# PSU_Schematic.net
KiCad netlist of a schematic drawn in EAGLE
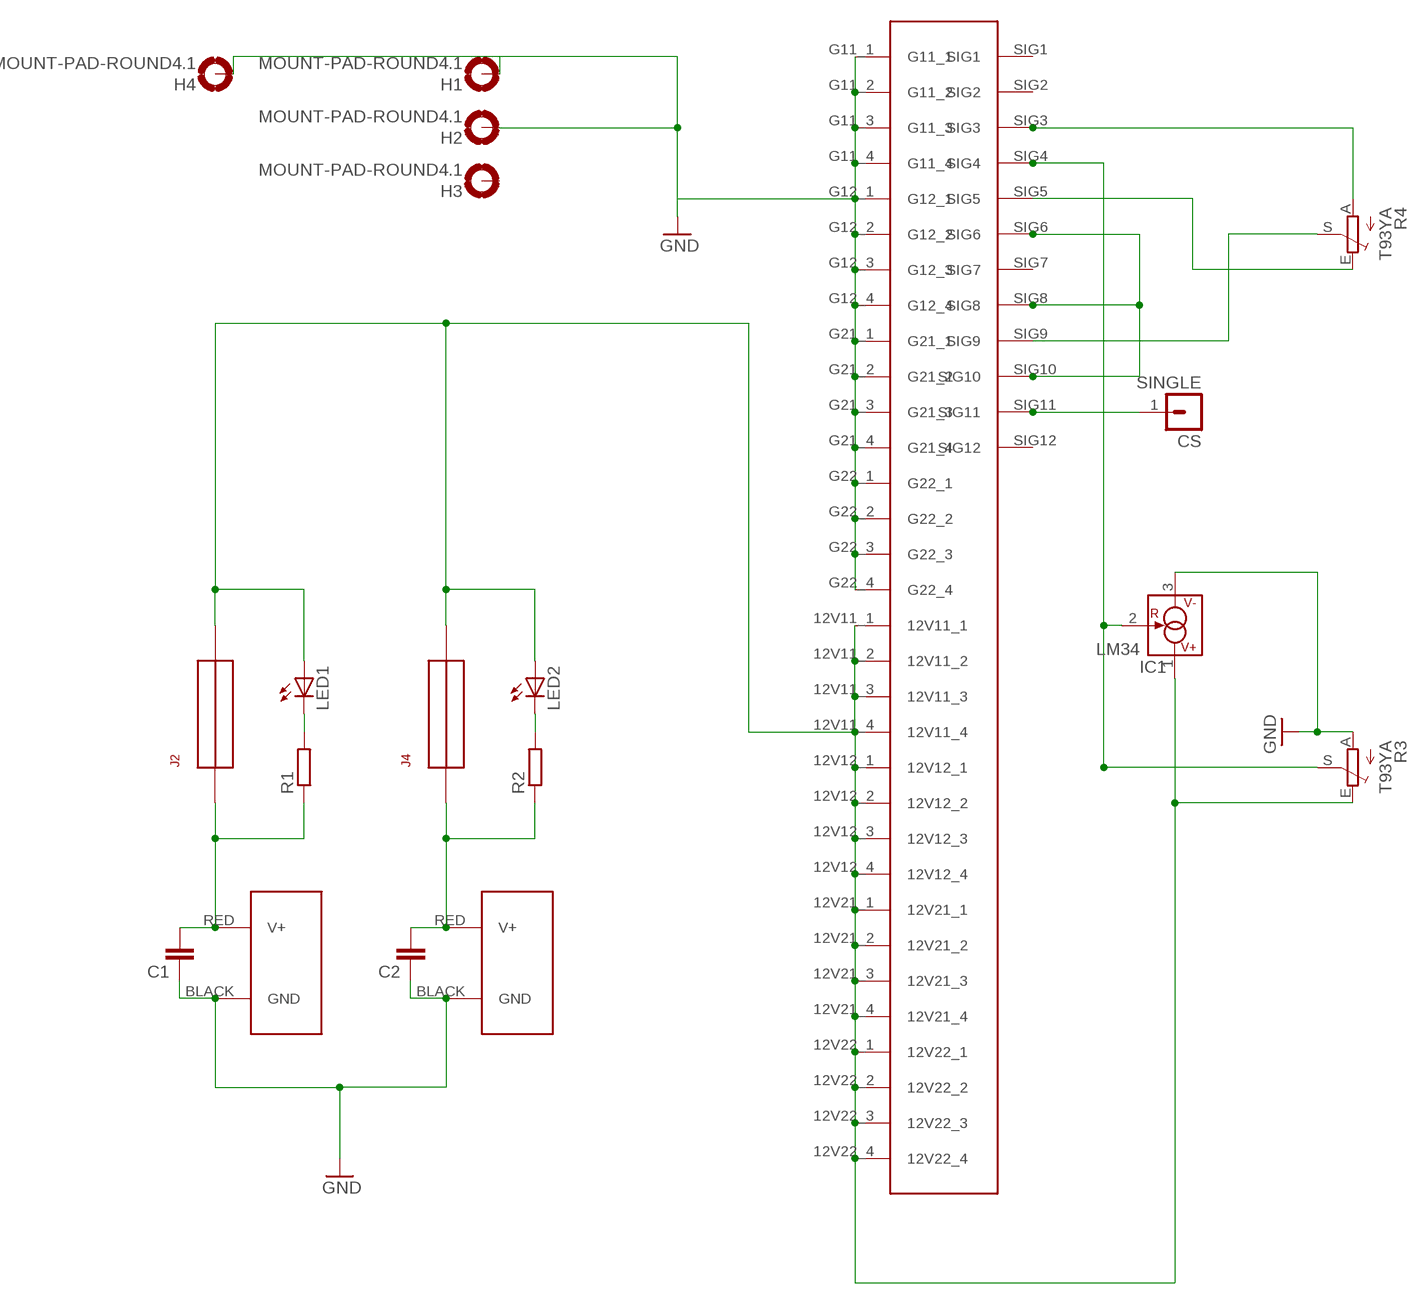
[diagram p0: schematic, sheet 1]

(export (version "E")
  (design (tool "Eeschema 10.0.6"))
  (components
    (comp (ref "C1")
      (value "C-EU050-025X075")
      (footprint "eagle-import:C050-025X075")
      (libsource (lib "eagle-import") (part "C-EU050-025X075"))
    )
    (comp (ref "C2")
      (value "C-EU050-025X075")
      (footprint "eagle-import:C050-025X075")
      (libsource (lib "eagle-import") (part "C-EU050-025X075"))
    )
    (comp (ref "CS")
      (value "SINGLE")
      (footprint "eagle-import:SINGLE")
      (libsource (lib "eagle-import") (part "SINGLE"))
    )
    (comp (ref "H1")
      (value "MOUNT-PAD-ROUND4.1")
      (footprint "eagle-import:4,1-PAD")
      (libsource (lib "eagle-import") (part "MOUNT-PAD-ROUND4.1"))
    )
    (comp (ref "H2")
      (value "MOUNT-PAD-ROUND4.1")
      (footprint "eagle-import:4,1-PAD")
      (libsource (lib "eagle-import") (part "MOUNT-PAD-ROUND4.1"))
    )
    (comp (ref "H3")
      (value "MOUNT-PAD-ROUND4.1")
      (footprint "eagle-import:4,1-PAD")
      (libsource (lib "eagle-import") (part "MOUNT-PAD-ROUND4.1"))
    )
    (comp (ref "H4")
      (value "MOUNT-PAD-ROUND4.1")
      (footprint "eagle-import:4,1-PAD")
      (libsource (lib "eagle-import") (part "MOUNT-PAD-ROUND4.1"))
    )
    (comp (ref "IC1")
      (value "LM34")
      (footprint "eagle-import:TO92")
      (libsource (lib "eagle-import") (part "LM34Z3"))
    )
    (comp (ref "J1")
      (value "POWERPOLE_POWER45A")
      (footprint "eagle-import:POWERPOLE_PAIR_45A")
      (libsource (lib "eagle-import") (part "POWERPOLE_POWER45A"))
    )
    (comp (ref "J2")
      (value "FUSEATC")
      (footprint "eagle-import:FUSE_ATC")
      (libsource (lib "eagle-import") (part "FUSEATC"))
    )
    (comp (ref "J3")
      (value "POWERPOLE_POWER45A")
      (footprint "eagle-import:POWERPOLE_PAIR_45A")
      (libsource (lib "eagle-import") (part "POWERPOLE_POWER45A"))
    )
    (comp (ref "J4")
      (value "FUSEATC")
      (footprint "eagle-import:FUSE_ATC")
      (libsource (lib "eagle-import") (part "FUSEATC"))
    )
    (comp (ref "LED1")
      (value "LED3MM")
      (footprint "eagle-import:LED3MM")
      (libsource (lib "eagle-import") (part "LED3MM"))
    )
    (comp (ref "LED2")
      (value "LED3MM")
      (footprint "eagle-import:LED3MM")
      (libsource (lib "eagle-import") (part "LED3MM"))
    )
    (comp (ref "R1")
      (value "R-EU_0204/7")
      (footprint "eagle-import:0204_7")
      (libsource (lib "eagle-import") (part "R-EU_0204/7"))
    )
    (comp (ref "R2")
      (value "R-EU_0204/7")
      (footprint "eagle-import:0204_7")
      (libsource (lib "eagle-import") (part "R-EU_0204/7"))
    )
    (comp (ref "R3")
      (value "T93YA")
      (footprint "eagle-import:RJ9W")
      (libsource (lib "eagle-import") (part "TRIM_EU-RJ9W"))
    )
    (comp (ref "R4")
      (value "T93YA")
      (footprint "eagle-import:RJ9W")
      (libsource (lib "eagle-import") (part "TRIM_EU-RJ9W"))
    )
    (comp (ref "U$2")
      (value "51760-10201202AALF51760-10201202AALF")
      (footprint "eagle-import:51730-073LF")
      (libsource (lib "eagle-import") (part "51760-10201202AALF51760-10201202AALF"))
    )
  )
  (nets
    (net (code "1") (name "GND") (class "Default")
      (node (ref "C1") (pin "1") (pinfunction "1_1") (pintype "passive"))
      (node (ref "C2") (pin "1") (pinfunction "1_1") (pintype "passive"))
      (node (ref "H1") (pin "B4,1") (pinfunction "MOUNT_B4,1") (pintype "passive"))
      (node (ref "H2") (pin "B4,1") (pinfunction "MOUNT_B4,1") (pintype "passive"))
      (node (ref "H4") (pin "B4,1") (pinfunction "MOUNT_B4,1") (pintype "passive"))
      (node (ref "IC1") (pin "3") (pinfunction "V-_3") (pintype "passive"))
      (node (ref "J1") (pin "BLACK") (pinfunction "GND_BLACK") (pintype "power_in"))
      (node (ref "J3") (pin "BLACK") (pinfunction "GND_BLACK") (pintype "power_in"))
      (node (ref "R3") (pin "A") (pinfunction "A_A") (pintype "passive"))
      (node (ref "U$2") (pin "G11_1") (pinfunction "G11_1_G11_1") (pintype "bidirectional"))
      (node (ref "U$2") (pin "G11_2") (pinfunction "G11_2_G11_2") (pintype "bidirectional"))
      (node (ref "U$2") (pin "G11_3") (pinfunction "G11_3_G11_3") (pintype "bidirectional"))
      (node (ref "U$2") (pin "G11_4") (pinfunction "G11_4_G11_4") (pintype "bidirectional"))
      (node (ref "U$2") (pin "G12_1") (pinfunction "G12_1_G12_1") (pintype "bidirectional"))
      (node (ref "U$2") (pin "G12_2") (pinfunction "G12_2_G12_2") (pintype "bidirectional"))
      (node (ref "U$2") (pin "G12_3") (pinfunction "G12_3_G12_3") (pintype "bidirectional"))
      (node (ref "U$2") (pin "G12_4") (pinfunction "G12_4_G12_4") (pintype "bidirectional"))
      (node (ref "U$2") (pin "G21_1") (pinfunction "G21_1_G21_1") (pintype "bidirectional"))
      (node (ref "U$2") (pin "G21_2") (pinfunction "G21_2_G21_2") (pintype "bidirectional"))
      (node (ref "U$2") (pin "G21_3") (pinfunction "G21_3_G21_3") (pintype "bidirectional"))
      (node (ref "U$2") (pin "G21_4") (pinfunction "G21_4_G21_4") (pintype "bidirectional"))
      (node (ref "U$2") (pin "G22_1") (pinfunction "G22_1_G22_1") (pintype "bidirectional"))
      (node (ref "U$2") (pin "G22_2") (pinfunction "G22_2_G22_2") (pintype "bidirectional"))
      (node (ref "U$2") (pin "G22_3") (pinfunction "G22_3_G22_3") (pintype "bidirectional"))
      (node (ref "U$2") (pin "G22_4") (pinfunction "G22_4_G22_4") (pintype "bidirectional"))
    )
    (net (code "2") (name "Net-(CS-3)") (class "Default")
      (node (ref "CS") (pin "1") (pinfunction "3_1") (pintype "passive"))
      (node (ref "U$2") (pin "SIG11") (pinfunction "SIG11_SIG11") (pintype "bidirectional"))
    )
    (net (code "3") (name "Net-(IC1-R)") (class "Default")
      (node (ref "IC1") (pin "2") (pinfunction "R_2") (pintype "passive"))
      (node (ref "R3") (pin "S") (pinfunction "S_S") (pintype "passive"))
      (node (ref "U$2") (pin "SIG4") (pinfunction "SIG4_SIG4") (pintype "bidirectional"))
    )
    (net (code "4") (name "Net-(IC1-V+)") (class "Default")
      (node (ref "IC1") (pin "1") (pinfunction "V+_1") (pintype "passive"))
      (node (ref "J2") (pin "P$3") (pinfunction "P$2_P$3") (pintype "bidirectional"))
      (node (ref "J2") (pin "P$4") (pinfunction "P$2_P$4") (pintype "bidirectional"))
      (node (ref "J4") (pin "P$3") (pinfunction "P$2_P$3") (pintype "bidirectional"))
      (node (ref "J4") (pin "P$4") (pinfunction "P$2_P$4") (pintype "bidirectional"))
      (node (ref "LED1") (pin "A") (pinfunction "A_A") (pintype "passive"))
      (node (ref "LED2") (pin "A") (pinfunction "A_A") (pintype "passive"))
      (node (ref "R3") (pin "E") (pinfunction "E_E") (pintype "passive"))
      (node (ref "U$2") (pin "12V11_1") (pinfunction "12V11_1_12V11_1") (pintype "bidirectional"))
      (node (ref "U$2") (pin "12V11_2") (pinfunction "12V11_2_12V11_2") (pintype "bidirectional"))
      (node (ref "U$2") (pin "12V11_3") (pinfunction "12V11_3_12V11_3") (pintype "bidirectional"))
      (node (ref "U$2") (pin "12V11_4") (pinfunction "12V11_4_12V11_4") (pintype "bidirectional"))
      (node (ref "U$2") (pin "12V12_1") (pinfunction "12V12_1_12V12_1") (pintype "bidirectional"))
      (node (ref "U$2") (pin "12V12_2") (pinfunction "12V12_2_12V12_2") (pintype "bidirectional"))
      (node (ref "U$2") (pin "12V12_3") (pinfunction "12V12_3_12V12_3") (pintype "bidirectional"))
      (node (ref "U$2") (pin "12V12_4") (pinfunction "12V12_4_12V12_4") (pintype "bidirectional"))
      (node (ref "U$2") (pin "12V21_1") (pinfunction "12V21_1_12V21_1") (pintype "bidirectional"))
      (node (ref "U$2") (pin "12V21_2") (pinfunction "12V21_2_12V21_2") (pintype "bidirectional"))
      (node (ref "U$2") (pin "12V21_3") (pinfunction "12V21_3_12V21_3") (pintype "bidirectional"))
      (node (ref "U$2") (pin "12V21_4") (pinfunction "12V21_4_12V21_4") (pintype "bidirectional"))
      (node (ref "U$2") (pin "12V22_1") (pinfunction "12V22_1_12V22_1") (pintype "bidirectional"))
      (node (ref "U$2") (pin "12V22_2") (pinfunction "12V22_2_12V22_2") (pintype "bidirectional"))
      (node (ref "U$2") (pin "12V22_3") (pinfunction "12V22_3_12V22_3") (pintype "bidirectional"))
      (node (ref "U$2") (pin "12V22_4") (pinfunction "12V22_4_12V22_4") (pintype "bidirectional"))
    )
    (net (code "5") (name "Net-(J1-V+)") (class "Default")
      (node (ref "C1") (pin "2") (pinfunction "2_2") (pintype "passive"))
      (node (ref "J1") (pin "RED") (pinfunction "V+_RED") (pintype "power_in"))
      (node (ref "J2") (pin "P$1") (pinfunction "P$1_P$1") (pintype "bidirectional"))
      (node (ref "J2") (pin "P$2") (pinfunction "P$1_P$2") (pintype "bidirectional"))
      (node (ref "R1") (pin "1") (pinfunction "1_1") (pintype "passive"))
    )
    (net (code "6") (name "Net-(J3-V+)") (class "Default")
      (node (ref "C2") (pin "2") (pinfunction "2_2") (pintype "passive"))
      (node (ref "J3") (pin "RED") (pinfunction "V+_RED") (pintype "power_in"))
      (node (ref "J4") (pin "P$1") (pinfunction "P$1_P$1") (pintype "bidirectional"))
      (node (ref "J4") (pin "P$2") (pinfunction "P$1_P$2") (pintype "bidirectional"))
      (node (ref "R2") (pin "1") (pinfunction "1_1") (pintype "passive"))
    )
    (net (code "7") (name "Net-(LED1-C)") (class "Default")
      (node (ref "LED1") (pin "K") (pinfunction "C_K") (pintype "passive"))
      (node (ref "R1") (pin "2") (pinfunction "2_2") (pintype "passive"))
    )
    (net (code "8") (name "Net-(LED2-C)") (class "Default")
      (node (ref "LED2") (pin "K") (pinfunction "C_K") (pintype "passive"))
      (node (ref "R2") (pin "2") (pinfunction "2_2") (pintype "passive"))
    )
    (net (code "9") (name "Net-(R4-PadA)") (class "Default")
      (node (ref "R4") (pin "A") (pinfunction "A_A") (pintype "passive"))
      (node (ref "U$2") (pin "SIG3") (pinfunction "SIG3_SIG3") (pintype "bidirectional"))
    )
    (net (code "10") (name "Net-(R4-PadE)") (class "Default")
      (node (ref "R4") (pin "E") (pinfunction "E_E") (pintype "passive"))
      (node (ref "U$2") (pin "SIG5") (pinfunction "SIG5_SIG5") (pintype "bidirectional"))
    )
    (net (code "11") (name "Net-(R4-PadS)") (class "Default")
      (node (ref "R4") (pin "S") (pinfunction "S_S") (pintype "passive"))
      (node (ref "U$2") (pin "SIG9") (pinfunction "SIG9_SIG9") (pintype "bidirectional"))
    )
    (net (code "12") (name "Net-(U$2-PadSIG10)") (class "Default")
      (node (ref "U$2") (pin "SIG10") (pinfunction "SIG10_SIG10") (pintype "bidirectional"))
      (node (ref "U$2") (pin "SIG6") (pinfunction "SIG6_SIG6") (pintype "bidirectional"))
      (node (ref "U$2") (pin "SIG8") (pinfunction "SIG8_SIG8") (pintype "bidirectional"))
    )
    (net (code "13") (name "unconnected-(H3-MOUNT-PadB4,1)") (class "Default")
      (node (ref "H3") (pin "B4,1") (pinfunction "MOUNT_B4,1") (pintype "passive"))
    )
    (net (code "14") (name "unconnected-(U$2-PadSIG1)") (class "Default")
      (node (ref "U$2") (pin "SIG1") (pinfunction "SIG1_SIG1") (pintype "bidirectional"))
    )
    (net (code "15") (name "unconnected-(U$2-PadSIG2)") (class "Default")
      (node (ref "U$2") (pin "SIG2") (pinfunction "SIG2_SIG2") (pintype "bidirectional"))
    )
    (net (code "16") (name "unconnected-(U$2-PadSIG7)") (class "Default")
      (node (ref "U$2") (pin "SIG7") (pinfunction "SIG7_SIG7") (pintype "bidirectional"))
    )
    (net (code "17") (name "unconnected-(U$2-PadSIG12)") (class "Default")
      (node (ref "U$2") (pin "SIG12") (pinfunction "SIG12_SIG12") (pintype "bidirectional"))
    )
  )
)
